# loadcell.net
KiCad netlist of a schematic drawn in EAGLE
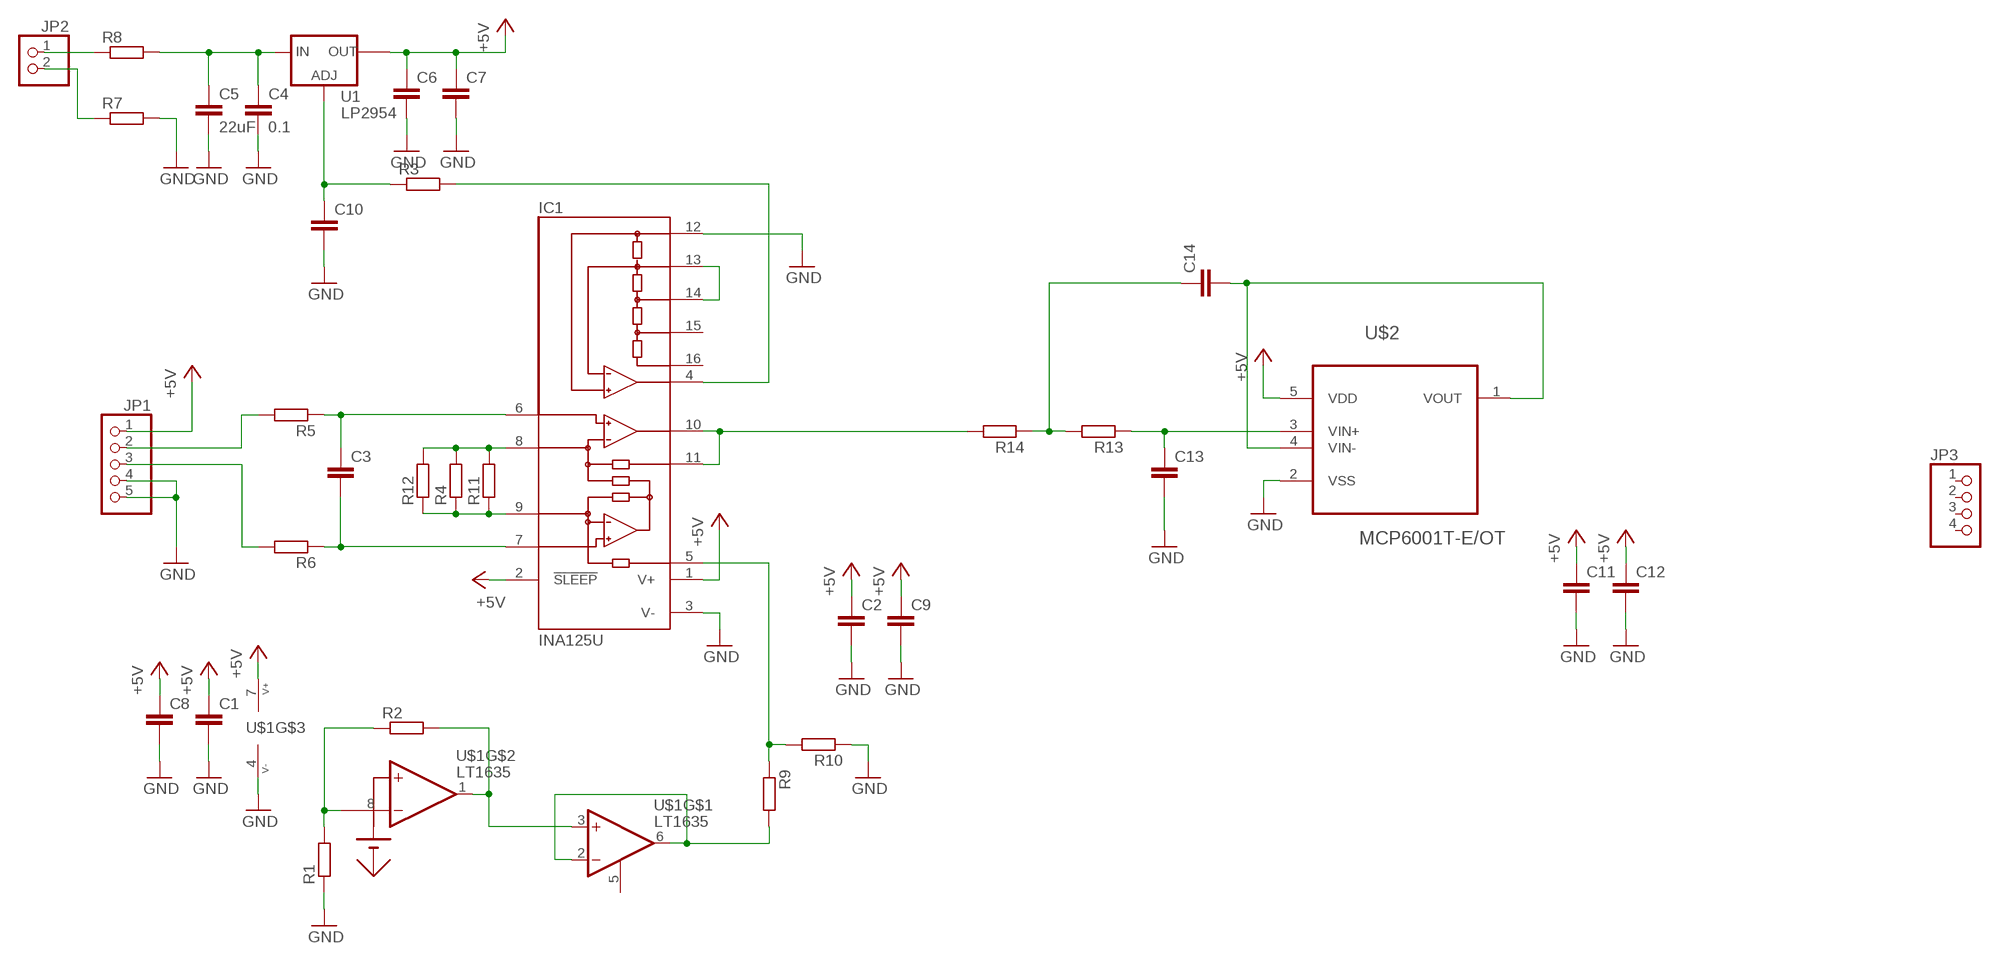
[diagram p0: schematic, sheet 1]

(export (version "E")
  (design (tool "Eeschema 10.0.6"))
  (components
    (comp (ref "C1")
      (value "C-EUC0805")
      (footprint "eagle-import:C0805")
      (libsource (lib "eagle-import") (part "C-EUC0805"))
    )
    (comp (ref "C2")
      (value "C-EUC0805")
      (footprint "eagle-import:C0805")
      (libsource (lib "eagle-import") (part "C-EUC0805"))
    )
    (comp (ref "C3")
      (value "C-EUC0805")
      (footprint "eagle-import:C0805")
      (libsource (lib "eagle-import") (part "C-EUC0805"))
    )
    (comp (ref "C4")
      (value "0.1")
      (footprint "eagle-import:C0805")
      (libsource (lib "eagle-import") (part "C-EUC0805"))
    )
    (comp (ref "C5")
      (value "22uF")
      (footprint "eagle-import:C0805")
      (libsource (lib "eagle-import") (part "C-EUC0805"))
    )
    (comp (ref "C6")
      (value "C-EUC0805")
      (footprint "eagle-import:C0805")
      (libsource (lib "eagle-import") (part "C-EUC0805"))
    )
    (comp (ref "C7")
      (value "C-EUC0805")
      (footprint "eagle-import:C0805")
      (libsource (lib "eagle-import") (part "C-EUC0805"))
    )
    (comp (ref "C8")
      (value "C-EUC0805")
      (footprint "eagle-import:C0805")
      (libsource (lib "eagle-import") (part "C-EUC0805"))
    )
    (comp (ref "C9")
      (value "C-EUC0805")
      (footprint "eagle-import:C0805")
      (libsource (lib "eagle-import") (part "C-EUC0805"))
    )
    (comp (ref "C10")
      (value "C-EUC0805")
      (footprint "eagle-import:C0805")
      (libsource (lib "eagle-import") (part "C-EUC0805"))
    )
    (comp (ref "C11")
      (value "C-EUC0805")
      (footprint "eagle-import:C0805")
      (libsource (lib "eagle-import") (part "C-EUC0805"))
    )
    (comp (ref "C12")
      (value "C-EUC0805")
      (footprint "eagle-import:C0805")
      (libsource (lib "eagle-import") (part "C-EUC0805"))
    )
    (comp (ref "C13")
      (value "C-EUC0805")
      (footprint "eagle-import:C0805")
      (libsource (lib "eagle-import") (part "C-EUC0805"))
    )
    (comp (ref "C14")
      (value "C-EUC0805")
      (footprint "eagle-import:C0805")
      (libsource (lib "eagle-import") (part "C-EUC0805"))
    )
    (comp (ref "IC1")
      (value "INA125U")
      (footprint "eagle-import:SO16-1")
      (libsource (lib "eagle-import") (part "INA125U"))
    )
    (comp (ref "JP1")
      (value "PINHD-1X5")
      (footprint "eagle-import:1X05")
      (libsource (lib "eagle-import") (part "PINHD-1X5"))
    )
    (comp (ref "JP2")
      (value "PINHD-1X2")
      (footprint "eagle-import:1X02")
      (libsource (lib "eagle-import") (part "PINHD-1X2"))
    )
    (comp (ref "JP3")
      (value "PINHD-1X4")
      (footprint "eagle-import:1X04")
      (libsource (lib "eagle-import") (part "PINHD-1X4"))
    )
    (comp (ref "R1")
      (value "R-EU_R0805")
      (footprint "eagle-import:R0805")
      (libsource (lib "eagle-import") (part "R-EU_R0805"))
    )
    (comp (ref "R2")
      (value "R-EU_R0805")
      (footprint "eagle-import:R0805")
      (libsource (lib "eagle-import") (part "R-EU_R0805"))
    )
    (comp (ref "R3")
      (value "R-EU_R0805")
      (footprint "eagle-import:R0805")
      (libsource (lib "eagle-import") (part "R-EU_R0805"))
    )
    (comp (ref "R4")
      (value "R-EU_R0805")
      (footprint "eagle-import:R0805")
      (libsource (lib "eagle-import") (part "R-EU_R0805"))
    )
    (comp (ref "R5")
      (value "R-EU_R0805")
      (footprint "eagle-import:R0805")
      (libsource (lib "eagle-import") (part "R-EU_R0805"))
    )
    (comp (ref "R6")
      (value "R-EU_R0805")
      (footprint "eagle-import:R0805")
      (libsource (lib "eagle-import") (part "R-EU_R0805"))
    )
    (comp (ref "R7")
      (value "R-EU_R0805")
      (footprint "eagle-import:R0805")
      (libsource (lib "eagle-import") (part "R-EU_R0805"))
    )
    (comp (ref "R8")
      (value "R-EU_R0805")
      (footprint "eagle-import:R0805")
      (libsource (lib "eagle-import") (part "R-EU_R0805"))
    )
    (comp (ref "R9")
      (value "R-EU_R0805")
      (footprint "eagle-import:R0805")
      (libsource (lib "eagle-import") (part "R-EU_R0805"))
    )
    (comp (ref "R10")
      (value "R-EU_R0805")
      (footprint "eagle-import:R0805")
      (libsource (lib "eagle-import") (part "R-EU_R0805"))
    )
    (comp (ref "R11")
      (value "R-EU_R0805")
      (footprint "eagle-import:R0805")
      (libsource (lib "eagle-import") (part "R-EU_R0805"))
    )
    (comp (ref "R12")
      (value "R-EU_R0805")
      (footprint "eagle-import:R0805")
      (libsource (lib "eagle-import") (part "R-EU_R0805"))
    )
    (comp (ref "R13")
      (value "R-EU_R0805")
      (footprint "eagle-import:R0805")
      (libsource (lib "eagle-import") (part "R-EU_R0805"))
    )
    (comp (ref "R14")
      (value "R-EU_R0805")
      (footprint "eagle-import:R0805")
      (libsource (lib "eagle-import") (part "R-EU_R0805"))
    )
    (comp (ref "U$1")
      (value "LT1635")
      (footprint "eagle-import:SO08")
      (libsource (lib "eagle-import") (part "LT1635"))
    )
    (comp (ref "U$2")
      (value "MCP6001T-E/OT")
      (footprint "eagle-import:SOT95P270X145-5N")
      (libsource (lib "eagle-import") (part "MCP6001T-E/OT"))
    )
    (comp (ref "U1")
      (value "LP2954")
      (footprint "eagle-import:TO263")
      (libsource (lib "eagle-import") (part "LM1084IS"))
    )
  )
  (nets
    (net (code "1") (name "+5V") (class "Default")
      (node (ref "C1") (pin "1") (pinfunction "1_1") (pintype "passive"))
      (node (ref "C11") (pin "1") (pinfunction "1_1") (pintype "passive"))
      (node (ref "C12") (pin "1") (pinfunction "1_1") (pintype "passive"))
      (node (ref "C2") (pin "1") (pinfunction "1_1") (pintype "passive"))
      (node (ref "C6") (pin "1") (pinfunction "1_1") (pintype "passive"))
      (node (ref "C7") (pin "1") (pinfunction "1_1") (pintype "passive"))
      (node (ref "C8") (pin "1") (pinfunction "1_1") (pintype "passive"))
      (node (ref "C9") (pin "1") (pinfunction "1_1") (pintype "passive"))
      (node (ref "IC1") (pin "1") (pinfunction "V+_1") (pintype "power_in"))
      (node (ref "IC1") (pin "2") (pinfunction "~{SLEEP}_2") (pintype "input"))
      (node (ref "JP1") (pin "1") (pinfunction "1_1") (pintype "passive"))
      (node (ref "U$1") (pin "7") (pinfunction "V+_7") (pintype "power_in"))
      (node (ref "U$2") (pin "5") (pinfunction "VDD_5") (pintype "power_in"))
      (node (ref "U1") (pin "2") (pinfunction "OUT_2") (pintype "passive"))
    )
    (net (code "2") (name "GND") (class "Default")
      (node (ref "C1") (pin "2") (pinfunction "2_2") (pintype "passive"))
      (node (ref "C10") (pin "2") (pinfunction "2_2") (pintype "passive"))
      (node (ref "C11") (pin "2") (pinfunction "2_2") (pintype "passive"))
      (node (ref "C12") (pin "2") (pinfunction "2_2") (pintype "passive"))
      (node (ref "C13") (pin "2") (pinfunction "2_2") (pintype "passive"))
      (node (ref "C2") (pin "2") (pinfunction "2_2") (pintype "passive"))
      (node (ref "C4") (pin "2") (pinfunction "2_2") (pintype "passive"))
      (node (ref "C5") (pin "2") (pinfunction "2_2") (pintype "passive"))
      (node (ref "C6") (pin "2") (pinfunction "2_2") (pintype "passive"))
      (node (ref "C7") (pin "2") (pinfunction "2_2") (pintype "passive"))
      (node (ref "C8") (pin "2") (pinfunction "2_2") (pintype "passive"))
      (node (ref "C9") (pin "2") (pinfunction "2_2") (pintype "passive"))
      (node (ref "IC1") (pin "12") (pinfunction "REFCOM_12") (pintype "passive"))
      (node (ref "IC1") (pin "3") (pinfunction "V-_3") (pintype "power_in"))
      (node (ref "JP1") (pin "4") (pinfunction "4_4") (pintype "passive"))
      (node (ref "JP1") (pin "5") (pinfunction "5_5") (pintype "passive"))
      (node (ref "R1") (pin "1") (pinfunction "1_1") (pintype "passive"))
      (node (ref "R10") (pin "1") (pinfunction "1_1") (pintype "passive"))
      (node (ref "R7") (pin "2") (pinfunction "2_2") (pintype "passive"))
      (node (ref "U$1") (pin "4") (pinfunction "V-_4") (pintype "power_in"))
      (node (ref "U$2") (pin "2") (pinfunction "VSS_2") (pintype "passive"))
    )
    (net (code "3") (name "Net-(C14-Pad1)") (class "Default")
      (node (ref "C14") (pin "1") (pinfunction "1_1") (pintype "passive"))
      (node (ref "R13") (pin "2") (pinfunction "2_2") (pintype "passive"))
      (node (ref "R14") (pin "1") (pinfunction "1_1") (pintype "passive"))
    )
    (net (code "4") (name "Net-(IC1-+IN)") (class "Default")
      (node (ref "C3") (pin "1") (pinfunction "1_1") (pintype "passive"))
      (node (ref "IC1") (pin "6") (pinfunction "+IN_6") (pintype "input"))
      (node (ref "R5") (pin "1") (pinfunction "1_1") (pintype "passive"))
    )
    (net (code "5") (name "Net-(IC1--IN)") (class "Default")
      (node (ref "C3") (pin "2") (pinfunction "2_2") (pintype "passive"))
      (node (ref "IC1") (pin "7") (pinfunction "-IN_7") (pintype "input"))
      (node (ref "R6") (pin "1") (pinfunction "1_1") (pintype "passive"))
    )
    (net (code "6") (name "Net-(IC1-OUT)") (class "Default")
      (node (ref "IC1") (pin "10") (pinfunction "OUT_10") (pintype "output"))
      (node (ref "IC1") (pin "11") (pinfunction "SENSE_11") (pintype "passive"))
      (node (ref "R14") (pin "2") (pinfunction "2_2") (pintype "passive"))
    )
    (net (code "7") (name "Net-(IC1-REF)") (class "Default")
      (node (ref "IC1") (pin "5") (pinfunction "REF_5") (pintype "passive"))
      (node (ref "R10") (pin "2") (pinfunction "2_2") (pintype "passive"))
      (node (ref "R9") (pin "1") (pinfunction "1_1") (pintype "passive"))
    )
    (net (code "8") (name "Net-(IC1-REF2.5)") (class "Default")
      (node (ref "IC1") (pin "13") (pinfunction "REFBG_13") (pintype "output"))
      (node (ref "IC1") (pin "14") (pinfunction "REF2.5_14") (pintype "output"))
    )
    (net (code "9") (name "Net-(IC1-REFOUT)") (class "Default")
      (node (ref "IC1") (pin "4") (pinfunction "REFOUT_4") (pintype "output"))
      (node (ref "R3") (pin "2") (pinfunction "2_2") (pintype "passive"))
    )
    (net (code "10") (name "Net-(IC1-RG-Pad8)") (class "Default")
      (node (ref "IC1") (pin "8") (pinfunction "RG_8") (pintype "passive"))
      (node (ref "R11") (pin "2") (pinfunction "2_2") (pintype "passive"))
      (node (ref "R12") (pin "2") (pinfunction "2_2") (pintype "passive"))
      (node (ref "R4") (pin "2") (pinfunction "2_2") (pintype "passive"))
    )
    (net (code "11") (name "Net-(IC1-RG-Pad9)") (class "Default")
      (node (ref "IC1") (pin "9") (pinfunction "RG_9") (pintype "passive"))
      (node (ref "R11") (pin "1") (pinfunction "1_1") (pintype "passive"))
      (node (ref "R12") (pin "1") (pinfunction "1_1") (pintype "passive"))
      (node (ref "R4") (pin "1") (pinfunction "1_1") (pintype "passive"))
    )
    (net (code "12") (name "Net-(JP1-Pad2)") (class "Default")
      (node (ref "JP1") (pin "2") (pinfunction "2_2") (pintype "passive"))
      (node (ref "R5") (pin "2") (pinfunction "2_2") (pintype "passive"))
    )
    (net (code "13") (name "Net-(JP1-Pad3)") (class "Default")
      (node (ref "JP1") (pin "3") (pinfunction "3_3") (pintype "passive"))
      (node (ref "R6") (pin "2") (pinfunction "2_2") (pintype "passive"))
    )
    (net (code "14") (name "Net-(JP2-Pad1)") (class "Default")
      (node (ref "JP2") (pin "1") (pinfunction "1_1") (pintype "passive"))
      (node (ref "R8") (pin "1") (pinfunction "1_1") (pintype "passive"))
    )
    (net (code "15") (name "Net-(JP2-Pad2)") (class "Default")
      (node (ref "JP2") (pin "2") (pinfunction "2_2") (pintype "passive"))
      (node (ref "R7") (pin "1") (pinfunction "1_1") (pintype "passive"))
    )
    (net (code "16") (name "Net-(U$1A-+IN)") (class "Default")
      (node (ref "R2") (pin "2") (pinfunction "2_2") (pintype "passive"))
      (node (ref "U$1") (pin "1") (pinfunction "REF_OUT_1") (pintype "output"))
      (node (ref "U$1") (pin "3") (pinfunction "+IN_3") (pintype "input"))
    )
    (net (code "17") (name "Net-(U$1A--IN)") (class "Default")
      (node (ref "R9") (pin "2") (pinfunction "2_2") (pintype "passive"))
      (node (ref "U$1") (pin "2") (pinfunction "-IN_2") (pintype "input"))
      (node (ref "U$1") (pin "6") (pinfunction "OUT_6") (pintype "output"))
    )
    (net (code "18") (name "Net-(U$1B-REF_FB)") (class "Default")
      (node (ref "R1") (pin "2") (pinfunction "2_2") (pintype "passive"))
      (node (ref "R2") (pin "1") (pinfunction "1_1") (pintype "passive"))
      (node (ref "U$1") (pin "8") (pinfunction "REF_FB_8") (pintype "input"))
    )
    (net (code "19") (name "Net-(U$2-VIN+)") (class "Default")
      (node (ref "C13") (pin "1") (pinfunction "1_1") (pintype "passive"))
      (node (ref "R13") (pin "1") (pinfunction "1_1") (pintype "passive"))
      (node (ref "U$2") (pin "3") (pinfunction "VIN+_3") (pintype "input"))
    )
    (net (code "20") (name "Net-(U$2-VIN-)") (class "Default")
      (node (ref "C14") (pin "2") (pinfunction "2_2") (pintype "passive"))
      (node (ref "U$2") (pin "1") (pinfunction "VOUT_1") (pintype "output"))
      (node (ref "U$2") (pin "4") (pinfunction "VIN-_4") (pintype "input"))
    )
    (net (code "21") (name "Net-(U1-ADJ)") (class "Default")
      (node (ref "C10") (pin "1") (pinfunction "1_1") (pintype "passive"))
      (node (ref "R3") (pin "1") (pinfunction "1_1") (pintype "passive"))
      (node (ref "U1") (pin "1") (pinfunction "ADJ_1") (pintype "input"))
    )
    (net (code "22") (name "Net-(U1-IN)") (class "Default")
      (node (ref "C4") (pin "1") (pinfunction "1_1") (pintype "passive"))
      (node (ref "C5") (pin "1") (pinfunction "1_1") (pintype "passive"))
      (node (ref "R8") (pin "2") (pinfunction "2_2") (pintype "passive"))
      (node (ref "U1") (pin "3") (pinfunction "IN_3") (pintype "input"))
    )
    (net (code "23") (name "unconnected-(IC1-REF5-Pad15)") (class "Default")
      (node (ref "IC1") (pin "15") (pinfunction "REF5_15") (pintype "output"))
    )
    (net (code "24") (name "unconnected-(IC1-REF10-Pad16)") (class "Default")
      (node (ref "IC1") (pin "16") (pinfunction "REF10_16") (pintype "output"))
    )
    (net (code "25") (name "unconnected-(JP3-Pad1)") (class "Default")
      (node (ref "JP3") (pin "1") (pinfunction "1_1") (pintype "passive"))
    )
    (net (code "26") (name "unconnected-(JP3-Pad2)") (class "Default")
      (node (ref "JP3") (pin "2") (pinfunction "2_2") (pintype "passive"))
    )
    (net (code "27") (name "unconnected-(JP3-Pad3)") (class "Default")
      (node (ref "JP3") (pin "3") (pinfunction "3_3") (pintype "passive"))
    )
    (net (code "28") (name "unconnected-(JP3-Pad4)") (class "Default")
      (node (ref "JP3") (pin "4") (pinfunction "4_4") (pintype "passive"))
    )
    (net (code "29") (name "unconnected-(U$1A-BAL-Pad5)") (class "Default")
      (node (ref "U$1") (pin "5") (pinfunction "BAL_5") (pintype "output"))
    )
    (net (code "30") (name "unconnected-(U1-OUT4-Pad4)") (class "Default")
      (node (ref "U1") (pin "4") (pinfunction "OUT4_4") (pintype "passive"))
    )
  )
)
